# ATSAMD21_board.net
KiCad netlist of a schematic drawn in EAGLE
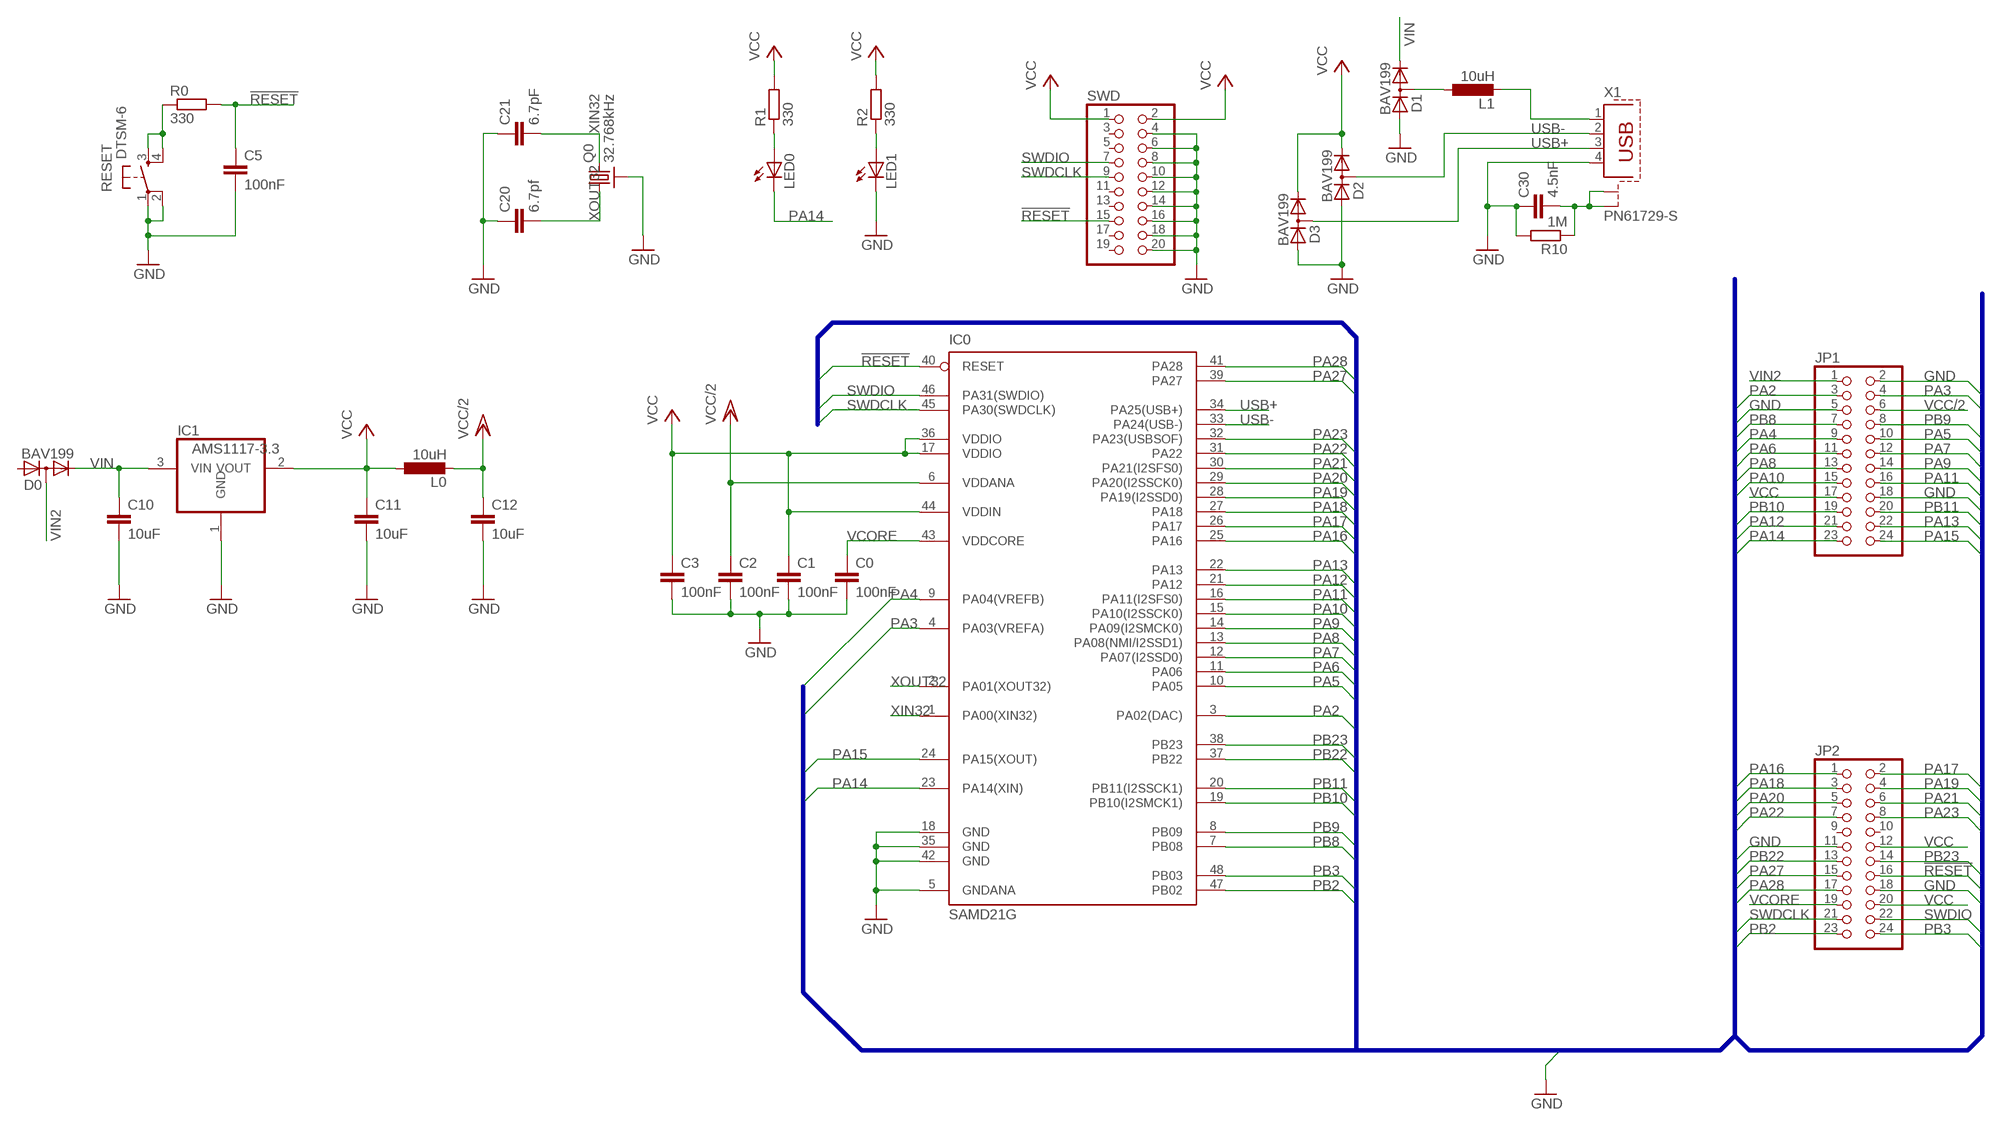
[diagram p0: schematic, sheet 1]

(export (version "E")
  (design (tool "Eeschema 10.0.6"))
  (components
    (comp (ref "C0")
      (value "100nF")
      (footprint "eagle-import:C0805K")
      (libsource (lib "eagle-import") (part "C-EUC0805K"))
    )
    (comp (ref "C1")
      (value "100nF")
      (footprint "eagle-import:C0805K")
      (libsource (lib "eagle-import") (part "C-EUC0805K"))
    )
    (comp (ref "C2")
      (value "100nF")
      (footprint "eagle-import:C0805K")
      (libsource (lib "eagle-import") (part "C-EUC0805K"))
    )
    (comp (ref "C3")
      (value "100nF")
      (footprint "eagle-import:C0805K")
      (libsource (lib "eagle-import") (part "C-EUC0805K"))
    )
    (comp (ref "C5")
      (value "100nF")
      (footprint "eagle-import:C0805K")
      (libsource (lib "eagle-import") (part "C-EUC0805K"))
    )
    (comp (ref "C10")
      (value "10uF")
      (footprint "eagle-import:C0805K")
      (libsource (lib "eagle-import") (part "C-EUC0805K"))
    )
    (comp (ref "C11")
      (value "10uF")
      (footprint "eagle-import:C0805K")
      (libsource (lib "eagle-import") (part "C-EUC0805K"))
    )
    (comp (ref "C12")
      (value "10uF")
      (footprint "eagle-import:C0805K")
      (libsource (lib "eagle-import") (part "C-EUC0805K"))
    )
    (comp (ref "C20")
      (value "6.7pf")
      (footprint "eagle-import:C0805K")
      (libsource (lib "eagle-import") (part "C-EUC0805K"))
    )
    (comp (ref "C21")
      (value "6.7pF")
      (footprint "eagle-import:C0805K")
      (libsource (lib "eagle-import") (part "C-EUC0805K"))
    )
    (comp (ref "C30")
      (value "4.5nF")
      (footprint "eagle-import:C0805K")
      (libsource (lib "eagle-import") (part "C-EUC0805K"))
    )
    (comp (ref "D0")
      (value "BAV199")
      (footprint "eagle-import:SOT23")
      (libsource (lib "eagle-import") (part "BAV199"))
    )
    (comp (ref "D1")
      (value "BAV199")
      (footprint "eagle-import:SOT23")
      (libsource (lib "eagle-import") (part "BAV199"))
    )
    (comp (ref "D2")
      (value "BAV199")
      (footprint "eagle-import:SOT23")
      (libsource (lib "eagle-import") (part "BAV199"))
    )
    (comp (ref "D3")
      (value "BAV199")
      (footprint "eagle-import:SOT23")
      (libsource (lib "eagle-import") (part "BAV199"))
    )
    (comp (ref "IC0")
      (value "SAMD21G")
      (footprint "eagle-import:TQFP48")
      (libsource (lib "eagle-import") (part "SAMD21G"))
    )
    (comp (ref "IC1")
      (value "AMS1117-3.3")
      (footprint "eagle-import:SOT223")
      (fields (field (name "MPN") "REG1117"))
      (libsource (lib "eagle-import") (part "REG1117"))
    )
    (comp (ref "JP1")
      (value "PINHD-2X12")
      (footprint "eagle-import:2X12")
      (libsource (lib "eagle-import") (part "PINHD-2X12"))
    )
    (comp (ref "JP2")
      (value "PINHD-2X12")
      (footprint "eagle-import:2X12")
      (libsource (lib "eagle-import") (part "PINHD-2X12"))
    )
    (comp (ref "L0")
      (value "10uH")
      (footprint "eagle-import:L2012C")
      (libsource (lib "eagle-import") (part "L-EUL2012C"))
    )
    (comp (ref "L1")
      (value "10uH")
      (footprint "eagle-import:L2012C")
      (libsource (lib "eagle-import") (part "L-EUL2012C"))
    )
    (comp (ref "LED0")
      (value "LEDCHIP-LED0805")
      (footprint "eagle-import:CHIP-LED0805")
      (libsource (lib "eagle-import") (part "LEDCHIP-LED0805"))
    )
    (comp (ref "LED1")
      (value "LEDCHIP-LED0805")
      (footprint "eagle-import:CHIP-LED0805")
      (libsource (lib "eagle-import") (part "LEDCHIP-LED0805"))
    )
    (comp (ref "Q0")
      (value "32.768kHz")
      (footprint "eagle-import:TC26H")
      (libsource (lib "eagle-import") (part "CRYSTALTC26H"))
    )
    (comp (ref "R0")
      (value "330")
      (footprint "eagle-import:R0805")
      (libsource (lib "eagle-import") (part "R-EU_R0805"))
    )
    (comp (ref "R1")
      (value "330")
      (footprint "eagle-import:R0805")
      (libsource (lib "eagle-import") (part "R-EU_R0805"))
    )
    (comp (ref "R2")
      (value "330")
      (footprint "eagle-import:R0805")
      (libsource (lib "eagle-import") (part "R-EU_R0805"))
    )
    (comp (ref "R10")
      (value "1M")
      (footprint "eagle-import:R0805")
      (libsource (lib "eagle-import") (part "R-EU_R0805"))
    )
    (comp (ref "RESET")
      (value "DTSM-6")
      (footprint "eagle-import:DTSM-6")
      (libsource (lib "eagle-import") (part "DTSM-6"))
    )
    (comp (ref "SWD")
      (value "PINHD-2X10")
      (footprint "eagle-import:2X10")
      (libsource (lib "eagle-import") (part "PINHD-2X10"))
    )
    (comp (ref "X1")
      (value "PN61729-S")
      (footprint "eagle-import:PN61729-S")
      (libsource (lib "eagle-import") (part "PN61729-S"))
    )
  )
  (nets
    (net (code "1") (name "/PA2") (class "Default")
      (node (ref "IC0") (pin "3") (pinfunction "PA02(DAC)_3") (pintype "bidirectional"))
      (node (ref "JP1") (pin "3") (pinfunction "3_3") (pintype "passive"))
    )
    (net (code "2") (name "/PA3") (class "Default")
      (node (ref "IC0") (pin "4") (pinfunction "PA03(VREFA)_4") (pintype "bidirectional"))
      (node (ref "JP1") (pin "4") (pinfunction "4_4") (pintype "passive"))
    )
    (net (code "3") (name "/PA4") (class "Default")
      (node (ref "IC0") (pin "9") (pinfunction "PA04(VREFB)_9") (pintype "bidirectional"))
      (node (ref "JP1") (pin "9") (pinfunction "9_9") (pintype "passive"))
    )
    (net (code "4") (name "/PA5") (class "Default")
      (node (ref "IC0") (pin "10") (pinfunction "PA05_10") (pintype "bidirectional"))
      (node (ref "JP1") (pin "10") (pinfunction "10_10") (pintype "passive"))
    )
    (net (code "5") (name "/PA6") (class "Default")
      (node (ref "IC0") (pin "11") (pinfunction "PA06_11") (pintype "bidirectional"))
      (node (ref "JP1") (pin "11") (pinfunction "11_11") (pintype "passive"))
    )
    (net (code "6") (name "/PA7") (class "Default")
      (node (ref "IC0") (pin "12") (pinfunction "PA07(I2SSD0)_12") (pintype "bidirectional"))
      (node (ref "JP1") (pin "12") (pinfunction "12_12") (pintype "passive"))
    )
    (net (code "7") (name "/PA8") (class "Default")
      (node (ref "IC0") (pin "13") (pinfunction "PA08(NMI/I2SSD1)_13") (pintype "bidirectional"))
      (node (ref "JP1") (pin "13") (pinfunction "13_13") (pintype "passive"))
    )
    (net (code "8") (name "/PA9") (class "Default")
      (node (ref "IC0") (pin "14") (pinfunction "PA09(I2SMCK0)_14") (pintype "bidirectional"))
      (node (ref "JP1") (pin "14") (pinfunction "14_14") (pintype "passive"))
    )
    (net (code "9") (name "/PA10") (class "Default")
      (node (ref "IC0") (pin "15") (pinfunction "PA10(I2SSCK0)_15") (pintype "bidirectional"))
      (node (ref "JP1") (pin "15") (pinfunction "15_15") (pintype "passive"))
    )
    (net (code "10") (name "/PA11") (class "Default")
      (node (ref "IC0") (pin "16") (pinfunction "PA11(I2SFS0)_16") (pintype "bidirectional"))
      (node (ref "JP1") (pin "16") (pinfunction "16_16") (pintype "passive"))
    )
    (net (code "11") (name "/PA12") (class "Default")
      (node (ref "IC0") (pin "21") (pinfunction "PA12_21") (pintype "bidirectional"))
      (node (ref "JP1") (pin "21") (pinfunction "21_21") (pintype "passive"))
    )
    (net (code "12") (name "/PA13") (class "Default")
      (node (ref "IC0") (pin "22") (pinfunction "PA13_22") (pintype "bidirectional"))
      (node (ref "JP1") (pin "22") (pinfunction "22_22") (pintype "passive"))
    )
    (net (code "13") (name "/PA14") (class "Default")
      (node (ref "IC0") (pin "23") (pinfunction "PA14(XIN)_23") (pintype "bidirectional"))
      (node (ref "JP1") (pin "23") (pinfunction "23_23") (pintype "passive"))
      (node (ref "LED0") (pin "C") (pinfunction "C_C") (pintype "passive"))
    )
    (net (code "14") (name "/PA15") (class "Default")
      (node (ref "IC0") (pin "24") (pinfunction "PA15(XOUT)_24") (pintype "bidirectional"))
      (node (ref "JP1") (pin "24") (pinfunction "24_24") (pintype "passive"))
    )
    (net (code "15") (name "/PA16") (class "Default")
      (node (ref "IC0") (pin "25") (pinfunction "PA16_25") (pintype "bidirectional"))
      (node (ref "JP2") (pin "1") (pinfunction "1_1") (pintype "passive"))
    )
    (net (code "16") (name "/PA17") (class "Default")
      (node (ref "IC0") (pin "26") (pinfunction "PA17_26") (pintype "bidirectional"))
      (node (ref "JP2") (pin "2") (pinfunction "2_2") (pintype "passive"))
    )
    (net (code "17") (name "/PA18") (class "Default")
      (node (ref "IC0") (pin "27") (pinfunction "PA18_27") (pintype "bidirectional"))
      (node (ref "JP2") (pin "3") (pinfunction "3_3") (pintype "passive"))
    )
    (net (code "18") (name "/PA19") (class "Default")
      (node (ref "IC0") (pin "28") (pinfunction "PA19(I2SSD0)_28") (pintype "bidirectional"))
      (node (ref "JP2") (pin "4") (pinfunction "4_4") (pintype "passive"))
    )
    (net (code "19") (name "/PA20") (class "Default")
      (node (ref "IC0") (pin "29") (pinfunction "PA20(I2SSCK0)_29") (pintype "bidirectional"))
      (node (ref "JP2") (pin "5") (pinfunction "5_5") (pintype "passive"))
    )
    (net (code "20") (name "/PA21") (class "Default")
      (node (ref "IC0") (pin "30") (pinfunction "PA21(I2SFS0)_30") (pintype "bidirectional"))
      (node (ref "JP2") (pin "6") (pinfunction "6_6") (pintype "passive"))
    )
    (net (code "21") (name "/PA22") (class "Default")
      (node (ref "IC0") (pin "31") (pinfunction "PA22_31") (pintype "bidirectional"))
      (node (ref "JP2") (pin "7") (pinfunction "7_7") (pintype "passive"))
    )
    (net (code "22") (name "/PA23") (class "Default")
      (node (ref "IC0") (pin "32") (pinfunction "PA23(USBSOF)_32") (pintype "bidirectional"))
      (node (ref "JP2") (pin "8") (pinfunction "8_8") (pintype "passive"))
    )
    (net (code "23") (name "/PA27") (class "Default")
      (node (ref "IC0") (pin "39") (pinfunction "PA27_39") (pintype "bidirectional"))
      (node (ref "JP2") (pin "15") (pinfunction "15_15") (pintype "passive"))
    )
    (net (code "24") (name "/PA28") (class "Default")
      (node (ref "IC0") (pin "41") (pinfunction "PA28_41") (pintype "bidirectional"))
      (node (ref "JP2") (pin "17") (pinfunction "17_17") (pintype "passive"))
    )
    (net (code "25") (name "/PB2") (class "Default")
      (node (ref "IC0") (pin "47") (pinfunction "PB02_47") (pintype "bidirectional"))
      (node (ref "JP2") (pin "23") (pinfunction "23_23") (pintype "passive"))
    )
    (net (code "26") (name "/PB3") (class "Default")
      (node (ref "IC0") (pin "48") (pinfunction "PB03_48") (pintype "bidirectional"))
      (node (ref "JP2") (pin "24") (pinfunction "24_24") (pintype "passive"))
    )
    (net (code "27") (name "/PB8") (class "Default")
      (node (ref "IC0") (pin "7") (pinfunction "PB08_7") (pintype "bidirectional"))
      (node (ref "JP1") (pin "7") (pinfunction "7_7") (pintype "passive"))
    )
    (net (code "28") (name "/PB9") (class "Default")
      (node (ref "IC0") (pin "8") (pinfunction "PB09_8") (pintype "bidirectional"))
      (node (ref "JP1") (pin "8") (pinfunction "8_8") (pintype "passive"))
    )
    (net (code "29") (name "/PB10") (class "Default")
      (node (ref "IC0") (pin "19") (pinfunction "PB10(I2SMCK1)_19") (pintype "bidirectional"))
      (node (ref "JP1") (pin "19") (pinfunction "19_19") (pintype "passive"))
    )
    (net (code "30") (name "/PB11") (class "Default")
      (node (ref "IC0") (pin "20") (pinfunction "PB11(I2SSCK1)_20") (pintype "bidirectional"))
      (node (ref "JP1") (pin "20") (pinfunction "20_20") (pintype "passive"))
    )
    (net (code "31") (name "/PB22") (class "Default")
      (node (ref "IC0") (pin "37") (pinfunction "PB22_37") (pintype "bidirectional"))
      (node (ref "JP2") (pin "13") (pinfunction "13_13") (pintype "passive"))
    )
    (net (code "32") (name "/PB23") (class "Default")
      (node (ref "IC0") (pin "38") (pinfunction "PB23_38") (pintype "bidirectional"))
      (node (ref "JP2") (pin "14") (pinfunction "14_14") (pintype "passive"))
    )
    (net (code "33") (name "/SWDCLK") (class "Default")
      (node (ref "IC0") (pin "45") (pinfunction "PA30(SWDCLK)_45") (pintype "bidirectional"))
      (node (ref "JP2") (pin "21") (pinfunction "21_21") (pintype "passive"))
      (node (ref "SWD") (pin "9") (pinfunction "9_9") (pintype "passive"))
    )
    (net (code "34") (name "/SWDIO") (class "Default")
      (node (ref "IC0") (pin "46") (pinfunction "PA31(SWDIO)_46") (pintype "bidirectional"))
      (node (ref "JP2") (pin "22") (pinfunction "22_22") (pintype "passive"))
      (node (ref "SWD") (pin "7") (pinfunction "7_7") (pintype "passive"))
    )
    (net (code "35") (name "/USB+") (class "Default")
      (node (ref "D3") (pin "3") (pinfunction "AC_3") (pintype "passive"))
      (node (ref "IC0") (pin "34") (pinfunction "PA25(USB+)_34") (pintype "bidirectional"))
      (node (ref "X1") (pin "3") (pinfunction "3_3") (pintype "passive"))
    )
    (net (code "36") (name "/USB-") (class "Default")
      (node (ref "D2") (pin "3") (pinfunction "AC_3") (pintype "passive"))
      (node (ref "IC0") (pin "33") (pinfunction "PA24(USB-)_33") (pintype "bidirectional"))
      (node (ref "X1") (pin "2") (pinfunction "2_2") (pintype "passive"))
    )
    (net (code "37") (name "/VCORE") (class "Default")
      (node (ref "C0") (pin "1") (pinfunction "1_1") (pintype "passive"))
      (node (ref "IC0") (pin "43") (pinfunction "VDDCORE_43") (pintype "power_in"))
      (node (ref "JP2") (pin "19") (pinfunction "19_19") (pintype "passive"))
    )
    (net (code "38") (name "/VIN") (class "Default")
      (node (ref "C10") (pin "1") (pinfunction "1_1") (pintype "passive"))
      (node (ref "D0") (pin "2") (pinfunction "C_2") (pintype "passive"))
      (node (ref "D1") (pin "2") (pinfunction "C_2") (pintype "passive"))
      (node (ref "IC1") (pin "3") (pinfunction "VIN_3") (pintype "input"))
    )
    (net (code "39") (name "/VIN2") (class "Default")
      (node (ref "D0") (pin "3") (pinfunction "AC_3") (pintype "passive"))
      (node (ref "JP1") (pin "1") (pinfunction "1_1") (pintype "passive"))
    )
    (net (code "40") (name "/XIN32") (class "Default")
      (node (ref "C21") (pin "2") (pinfunction "2_2") (pintype "passive"))
      (node (ref "IC0") (pin "1") (pinfunction "PA00(XIN32)_1") (pintype "bidirectional"))
      (node (ref "Q0") (pin "2") (pinfunction "2_2") (pintype "passive"))
    )
    (net (code "41") (name "/XOUT32") (class "Default")
      (node (ref "C20") (pin "2") (pinfunction "2_2") (pintype "passive"))
      (node (ref "IC0") (pin "2") (pinfunction "PA01(XOUT32)_2") (pintype "bidirectional"))
      (node (ref "Q0") (pin "1") (pinfunction "1_1") (pintype "passive"))
    )
    (net (code "42") (name "/~{RESET}") (class "Default")
      (node (ref "C5") (pin "1") (pinfunction "1_1") (pintype "passive"))
      (node (ref "IC0") (pin "40") (pinfunction "RESET_40") (pintype "bidirectional"))
      (node (ref "JP2") (pin "16") (pinfunction "16_16") (pintype "passive"))
      (node (ref "R0") (pin "2") (pinfunction "2_2") (pintype "passive"))
      (node (ref "SWD") (pin "15") (pinfunction "15_15") (pintype "passive"))
    )
    (net (code "43") (name "GND") (class "Default")
      (node (ref "C0") (pin "2") (pinfunction "2_2") (pintype "passive"))
      (node (ref "C1") (pin "2") (pinfunction "2_2") (pintype "passive"))
      (node (ref "C10") (pin "2") (pinfunction "2_2") (pintype "passive"))
      (node (ref "C11") (pin "2") (pinfunction "2_2") (pintype "passive"))
      (node (ref "C12") (pin "2") (pinfunction "2_2") (pintype "passive"))
      (node (ref "C2") (pin "2") (pinfunction "2_2") (pintype "passive"))
      (node (ref "C20") (pin "1") (pinfunction "1_1") (pintype "passive"))
      (node (ref "C21") (pin "1") (pinfunction "1_1") (pintype "passive"))
      (node (ref "C3") (pin "2") (pinfunction "2_2") (pintype "passive"))
      (node (ref "C30") (pin "1") (pinfunction "1_1") (pintype "passive"))
      (node (ref "C5") (pin "2") (pinfunction "2_2") (pintype "passive"))
      (node (ref "D1") (pin "1") (pinfunction "A_1") (pintype "passive"))
      (node (ref "D2") (pin "1") (pinfunction "A_1") (pintype "passive"))
      (node (ref "D3") (pin "1") (pinfunction "A_1") (pintype "passive"))
      (node (ref "IC0") (pin "18") (pinfunction "GND_18") (pintype "power_in"))
      (node (ref "IC0") (pin "35") (pinfunction "GND_35") (pintype "power_in"))
      (node (ref "IC0") (pin "42") (pinfunction "GND_42") (pintype "power_in"))
      (node (ref "IC0") (pin "5") (pinfunction "GNDANA_5") (pintype "power_in"))
      (node (ref "IC1") (pin "1") (pinfunction "GND_1") (pintype "power_in"))
      (node (ref "JP1") (pin "18") (pinfunction "18_18") (pintype "passive"))
      (node (ref "JP1") (pin "2") (pinfunction "2_2") (pintype "passive"))
      (node (ref "JP1") (pin "5") (pinfunction "5_5") (pintype "passive"))
      (node (ref "JP2") (pin "11") (pinfunction "11_11") (pintype "passive"))
      (node (ref "JP2") (pin "18") (pinfunction "18_18") (pintype "passive"))
      (node (ref "LED1") (pin "C") (pinfunction "C_C") (pintype "passive"))
      (node (ref "Q0") (pin "P$1") (pinfunction "3_P$1") (pintype "passive"))
      (node (ref "R10") (pin "2") (pinfunction "2_2") (pintype "passive"))
      (node (ref "RESET") (pin "1") (pinfunction "1_1") (pintype "passive"))
      (node (ref "RESET") (pin "2") (pinfunction "2_2") (pintype "passive"))
      (node (ref "SWD") (pin "10") (pinfunction "10_10") (pintype "passive"))
      (node (ref "SWD") (pin "12") (pinfunction "12_12") (pintype "passive"))
      (node (ref "SWD") (pin "14") (pinfunction "14_14") (pintype "passive"))
      (node (ref "SWD") (pin "16") (pinfunction "16_16") (pintype "passive"))
      (node (ref "SWD") (pin "18") (pinfunction "18_18") (pintype "passive"))
      (node (ref "SWD") (pin "20") (pinfunction "20_20") (pintype "passive"))
      (node (ref "SWD") (pin "4") (pinfunction "4_4") (pintype "passive"))
      (node (ref "SWD") (pin "6") (pinfunction "6_6") (pintype "passive"))
      (node (ref "SWD") (pin "8") (pinfunction "8_8") (pintype "passive"))
      (node (ref "X1") (pin "4") (pinfunction "4_4") (pintype "passive"))
    )
    (net (code "44") (name "Net-(C30-Pad2)") (class "Default")
      (node (ref "C30") (pin "2") (pinfunction "2_2") (pintype "passive"))
      (node (ref "R10") (pin "1") (pinfunction "1_1") (pintype "passive"))
      (node (ref "X1") (pin "S1") (pinfunction "S1_S1") (pintype "passive"))
      (node (ref "X1") (pin "S2") (pinfunction "S2_S2") (pintype "passive"))
    )
    (net (code "45") (name "Net-(D1-AC)") (class "Default")
      (node (ref "D1") (pin "3") (pinfunction "AC_3") (pintype "passive"))
      (node (ref "L1") (pin "1") (pinfunction "1_1") (pintype "passive"))
    )
    (net (code "46") (name "Net-(L1-Pad2)") (class "Default")
      (node (ref "L1") (pin "2") (pinfunction "2_2") (pintype "passive"))
      (node (ref "X1") (pin "1") (pinfunction "1_1") (pintype "passive"))
    )
    (net (code "47") (name "Net-(LED0-PadA)") (class "Default")
      (node (ref "LED0") (pin "A") (pinfunction "A_A") (pintype "passive"))
      (node (ref "R1") (pin "1") (pinfunction "1_1") (pintype "passive"))
    )
    (net (code "48") (name "Net-(LED1-PadA)") (class "Default")
      (node (ref "LED1") (pin "A") (pinfunction "A_A") (pintype "passive"))
      (node (ref "R2") (pin "1") (pinfunction "1_1") (pintype "passive"))
    )
    (net (code "49") (name "Net-(R0-Pad1)") (class "Default")
      (node (ref "R0") (pin "1") (pinfunction "1_1") (pintype "passive"))
      (node (ref "RESET") (pin "3") (pinfunction "3_3") (pintype "passive"))
      (node (ref "RESET") (pin "4") (pinfunction "4_4") (pintype "passive"))
    )
    (net (code "50") (name "VCC") (class "Default")
      (node (ref "C1") (pin "1") (pinfunction "1_1") (pintype "passive"))
      (node (ref "C11") (pin "1") (pinfunction "1_1") (pintype "passive"))
      (node (ref "C3") (pin "1") (pinfunction "1_1") (pintype "passive"))
      (node (ref "D2") (pin "2") (pinfunction "C_2") (pintype "passive"))
      (node (ref "D3") (pin "2") (pinfunction "C_2") (pintype "passive"))
      (node (ref "IC0") (pin "17") (pinfunction "VDDIO_17") (pintype "power_in"))
      (node (ref "IC0") (pin "36") (pinfunction "VDDIO_36") (pintype "power_in"))
      (node (ref "IC0") (pin "44") (pinfunction "VDDIN_44") (pintype "power_in"))
      (node (ref "IC1") (pin "2") (pinfunction "VOUT_2") (pintype "output"))
      (node (ref "JP1") (pin "17") (pinfunction "17_17") (pintype "passive"))
      (node (ref "JP2") (pin "12") (pinfunction "12_12") (pintype "passive"))
      (node (ref "JP2") (pin "20") (pinfunction "20_20") (pintype "passive"))
      (node (ref "L0") (pin "1") (pinfunction "1_1") (pintype "passive"))
      (node (ref "R1") (pin "2") (pinfunction "2_2") (pintype "passive"))
      (node (ref "R2") (pin "2") (pinfunction "2_2") (pintype "passive"))
      (node (ref "SWD") (pin "1") (pinfunction "1_1") (pintype "passive"))
      (node (ref "SWD") (pin "2") (pinfunction "2_2") (pintype "passive"))
    )
    (net (code "51") (name "VCC{slash}2") (class "Default")
      (node (ref "C12") (pin "1") (pinfunction "1_1") (pintype "passive"))
      (node (ref "C2") (pin "1") (pinfunction "1_1") (pintype "passive"))
      (node (ref "IC0") (pin "6") (pinfunction "VDDANA_6") (pintype "power_in"))
      (node (ref "JP1") (pin "6") (pinfunction "6_6") (pintype "passive"))
      (node (ref "L0") (pin "2") (pinfunction "2_2") (pintype "passive"))
    )
    (net (code "52") (name "unconnected-(D0-A-Pad1)") (class "Default")
      (node (ref "D0") (pin "1") (pinfunction "A_1") (pintype "passive"))
    )
    (net (code "53") (name "unconnected-(JP2-Pad9)") (class "Default")
      (node (ref "JP2") (pin "9") (pinfunction "9_9") (pintype "passive"))
    )
    (net (code "54") (name "unconnected-(JP2-Pad10)") (class "Default")
      (node (ref "JP2") (pin "10") (pinfunction "10_10") (pintype "passive"))
    )
    (net (code "55") (name "unconnected-(SWD-Pad3)") (class "Default")
      (node (ref "SWD") (pin "3") (pinfunction "3_3") (pintype "passive"))
    )
    (net (code "56") (name "unconnected-(SWD-Pad5)") (class "Default")
      (node (ref "SWD") (pin "5") (pinfunction "5_5") (pintype "passive"))
    )
    (net (code "57") (name "unconnected-(SWD-Pad11)") (class "Default")
      (node (ref "SWD") (pin "11") (pinfunction "11_11") (pintype "passive"))
    )
    (net (code "58") (name "unconnected-(SWD-Pad13)") (class "Default")
      (node (ref "SWD") (pin "13") (pinfunction "13_13") (pintype "passive"))
    )
    (net (code "59") (name "unconnected-(SWD-Pad17)") (class "Default")
      (node (ref "SWD") (pin "17") (pinfunction "17_17") (pintype "passive"))
    )
    (net (code "60") (name "unconnected-(SWD-Pad19)") (class "Default")
      (node (ref "SWD") (pin "19") (pinfunction "19_19") (pintype "passive"))
    )
  )
)
